# nixie2.net
KiCad netlist of a schematic drawn in EAGLE
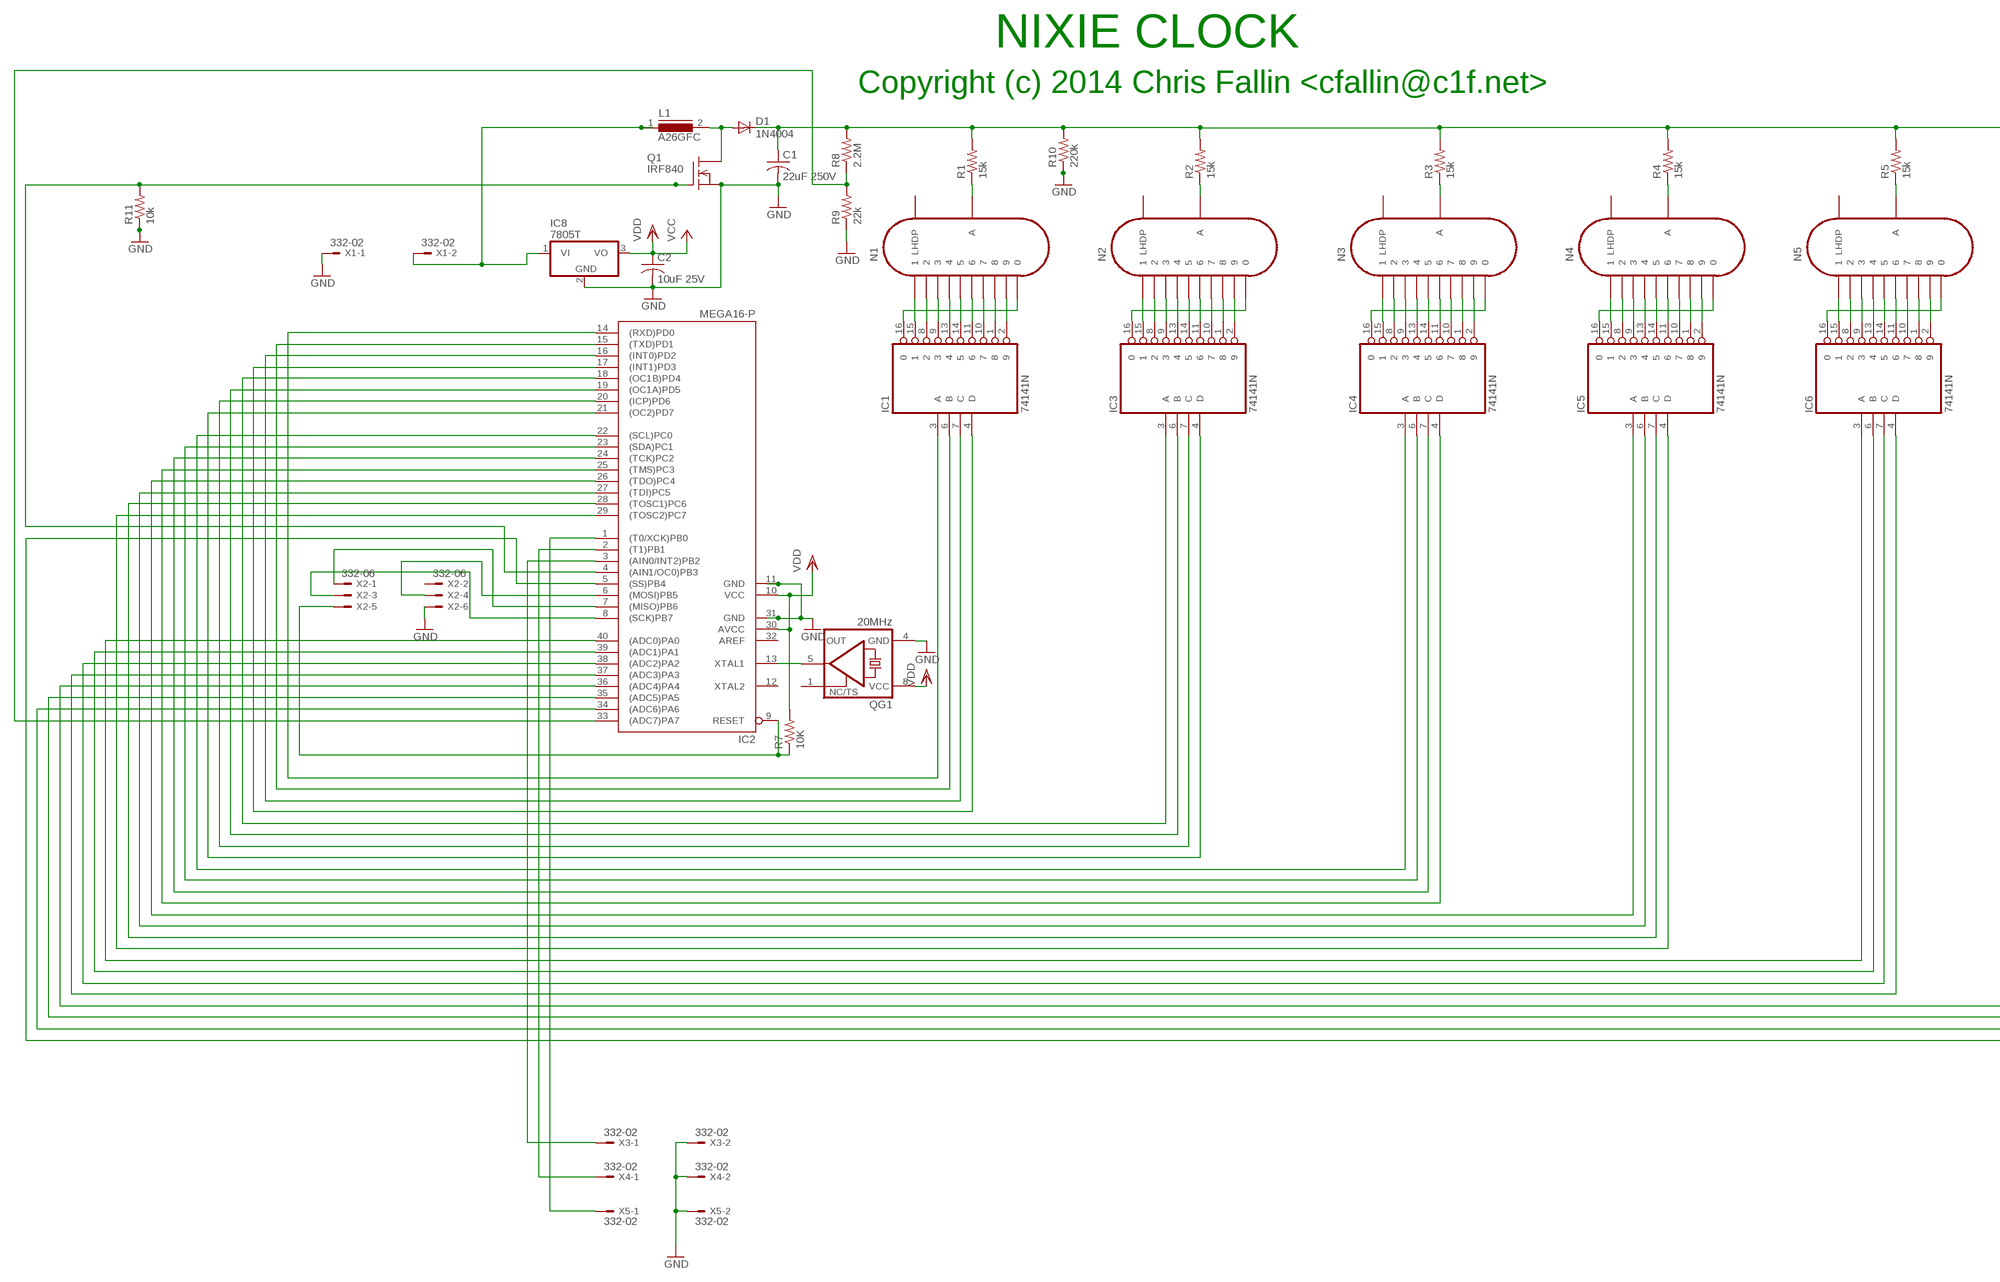
[diagram p0: schematic, sheet 1, part 1 of 2]
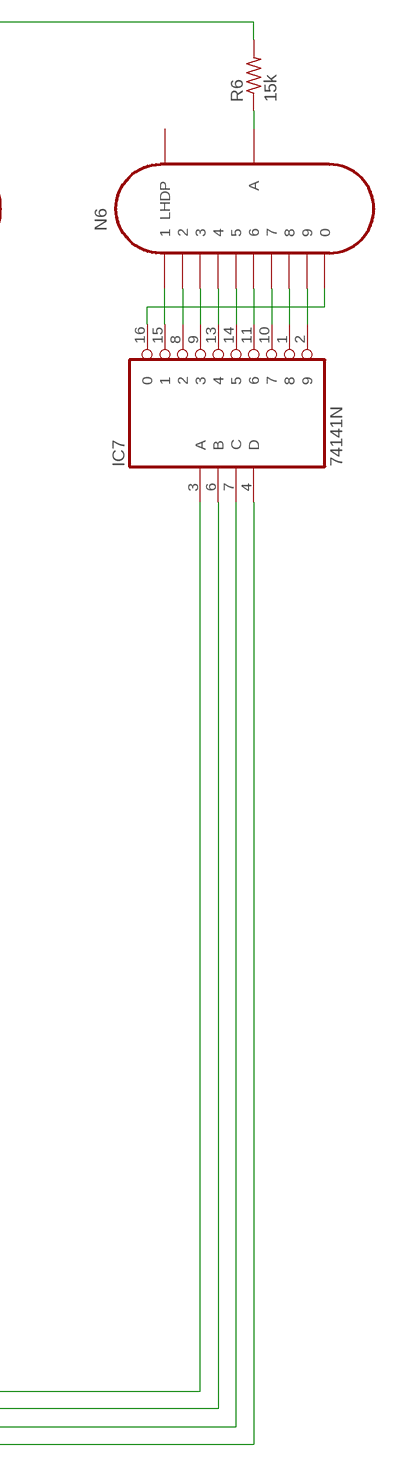
[diagram p1: schematic, sheet 1, part 2 of 2]

(export (version "E")
  (design (tool "Eeschema 10.0.6"))
  (components
    (comp (ref "C1")
      (value "22uF 250V")
      (footprint "eagle-import:C050-075X075")
      (libsource (lib "eagle-import") (part "C-US050-075X075"))
    )
    (comp (ref "C2")
      (value "10uF 25V")
      (footprint "eagle-import:C050-075X075")
      (libsource (lib "eagle-import") (part "C-US050-075X075"))
    )
    (comp (ref "D1")
      (value "1N4004")
      (footprint "eagle-import:DO41-10")
      (libsource (lib "eagle-import") (part "1N4004"))
    )
    (comp (ref "IC1")
      (value "74141N")
      (footprint "eagle-import:DIL16")
      (libsource (lib "eagle-import") (part "74141N"))
    )
    (comp (ref "IC2")
      (value "MEGA16-P")
      (footprint "eagle-import:DIL40")
      (fields (field (name "MPN") "ATMEGA16-16PU"))
      (libsource (lib "eagle-import") (part "MEGA16-P"))
    )
    (comp (ref "IC3")
      (value "74141N")
      (footprint "eagle-import:DIL16")
      (libsource (lib "eagle-import") (part "74141N"))
    )
    (comp (ref "IC4")
      (value "74141N")
      (footprint "eagle-import:DIL16")
      (libsource (lib "eagle-import") (part "74141N"))
    )
    (comp (ref "IC5")
      (value "74141N")
      (footprint "eagle-import:DIL16")
      (libsource (lib "eagle-import") (part "74141N"))
    )
    (comp (ref "IC6")
      (value "74141N")
      (footprint "eagle-import:DIL16")
      (libsource (lib "eagle-import") (part "74141N"))
    )
    (comp (ref "IC7")
      (value "74141N")
      (footprint "eagle-import:DIL16")
      (libsource (lib "eagle-import") (part "74141N"))
    )
    (comp (ref "IC8")
      (value "7805T")
      (footprint "eagle-import:TO220H")
      (libsource (lib "eagle-import") (part "78T05"))
    )
    (comp (ref "L1")
      (value "A26GFC")
      (footprint "eagle-import:A26GFC")
      (libsource (lib "eagle-import") (part "A26GFC"))
    )
    (comp (ref "N1")
      (value "IN-12B")
      (footprint "eagle-import:IN-12")
      (libsource (lib "eagle-import") (part "IN-12B"))
    )
    (comp (ref "N2")
      (value "IN-12B")
      (footprint "eagle-import:IN-12")
      (libsource (lib "eagle-import") (part "IN-12B"))
    )
    (comp (ref "N3")
      (value "IN-12B")
      (footprint "eagle-import:IN-12")
      (libsource (lib "eagle-import") (part "IN-12B"))
    )
    (comp (ref "N4")
      (value "IN-12B")
      (footprint "eagle-import:IN-12")
      (libsource (lib "eagle-import") (part "IN-12B"))
    )
    (comp (ref "N5")
      (value "IN-12B")
      (footprint "eagle-import:IN-12")
      (libsource (lib "eagle-import") (part "IN-12B"))
    )
    (comp (ref "N6")
      (value "IN-12B")
      (footprint "eagle-import:IN-12")
      (libsource (lib "eagle-import") (part "IN-12B"))
    )
    (comp (ref "Q1")
      (value "IRF840")
      (footprint "eagle-import:TO220")
      (libsource (lib "eagle-import") (part "IRF840"))
    )
    (comp (ref "QG1")
      (value "20MHz")
      (footprint "eagle-import:DIL08S")
      (libsource (lib "eagle-import") (part "XO-8"))
    )
    (comp (ref "R1")
      (value "15k")
      (footprint "eagle-import:0204V")
      (libsource (lib "eagle-import") (part "R-US_0204/2V"))
    )
    (comp (ref "R2")
      (value "15k")
      (footprint "eagle-import:0204V")
      (libsource (lib "eagle-import") (part "R-US_0204/2V"))
    )
    (comp (ref "R3")
      (value "15k")
      (footprint "eagle-import:0204V")
      (libsource (lib "eagle-import") (part "R-US_0204/2V"))
    )
    (comp (ref "R4")
      (value "15k")
      (footprint "eagle-import:0204V")
      (libsource (lib "eagle-import") (part "R-US_0204/2V"))
    )
    (comp (ref "R5")
      (value "15k")
      (footprint "eagle-import:0204V")
      (libsource (lib "eagle-import") (part "R-US_0204/2V"))
    )
    (comp (ref "R6")
      (value "15k")
      (footprint "eagle-import:0204V")
      (libsource (lib "eagle-import") (part "R-US_0204/2V"))
    )
    (comp (ref "R7")
      (value "10K")
      (footprint "eagle-import:0204V")
      (libsource (lib "eagle-import") (part "R-US_0204/2V"))
    )
    (comp (ref "R8")
      (value "2.2M")
      (footprint "eagle-import:0204V")
      (libsource (lib "eagle-import") (part "R-US_0204/2V"))
    )
    (comp (ref "R9")
      (value "22k")
      (footprint "eagle-import:0204V")
      (libsource (lib "eagle-import") (part "R-US_0204/2V"))
    )
    (comp (ref "R10")
      (value "220k")
      (footprint "eagle-import:0204V")
      (libsource (lib "eagle-import") (part "R-US_0204/2V"))
    )
    (comp (ref "R11")
      (value "10k")
      (footprint "eagle-import:0204V")
      (libsource (lib "eagle-import") (part "R-US_0204/2V"))
    )
    (comp (ref "X1")
      (value "332-02")
      (footprint "eagle-import:332-02")
      (libsource (lib "eagle-import") (part "332-02"))
    )
    (comp (ref "X2")
      (value "332-06")
      (footprint "eagle-import:332-06")
      (libsource (lib "eagle-import") (part "332-06"))
    )
    (comp (ref "X3")
      (value "332-02")
      (footprint "eagle-import:332-02")
      (libsource (lib "eagle-import") (part "332-02"))
    )
    (comp (ref "X4")
      (value "332-02")
      (footprint "eagle-import:332-02")
      (libsource (lib "eagle-import") (part "332-02"))
    )
    (comp (ref "X5")
      (value "332-02")
      (footprint "eagle-import:332-02")
      (libsource (lib "eagle-import") (part "332-02"))
    )
  )
  (nets
    (net (code "1") (name "GND") (class "Default")
      (node (ref "C1") (pin "2") (pinfunction "2_2") (pintype "passive"))
      (node (ref "C2") (pin "2") (pinfunction "2_2") (pintype "passive"))
      (node (ref "IC2") (pin "11") (pinfunction "GND_11") (pintype "power_in"))
      (node (ref "IC2") (pin "31") (pinfunction "GND_31") (pintype "power_in"))
      (node (ref "IC8") (pin "2") (pinfunction "GND_2") (pintype "passive"))
      (node (ref "Q1") (pin "3") (pinfunction "S_3") (pintype "passive"))
      (node (ref "QG1") (pin "4") (pinfunction "GND_4") (pintype "power_in"))
      (node (ref "R10") (pin "1") (pinfunction "1_1") (pintype "passive"))
      (node (ref "R11") (pin "1") (pinfunction "1_1") (pintype "passive"))
      (node (ref "R9") (pin "1") (pinfunction "1_1") (pintype "passive"))
      (node (ref "X1") (pin "1") (pinfunction "S_1") (pintype "passive"))
      (node (ref "X2") (pin "6") (pinfunction "S_6") (pintype "passive"))
      (node (ref "X3") (pin "2") (pinfunction "S_2") (pintype "passive"))
      (node (ref "X4") (pin "2") (pinfunction "S_2") (pintype "passive"))
      (node (ref "X5") (pin "2") (pinfunction "S_2") (pintype "passive"))
    )
    (net (code "2") (name "Net-(C1-Pad1)") (class "Default")
      (node (ref "C1") (pin "1") (pinfunction "1_1") (pintype "passive"))
      (node (ref "D1") (pin "C") (pinfunction "C_C") (pintype "passive"))
      (node (ref "R1") (pin "2") (pinfunction "2_2") (pintype "passive"))
      (node (ref "R10") (pin "2") (pinfunction "2_2") (pintype "passive"))
      (node (ref "R2") (pin "2") (pinfunction "2_2") (pintype "passive"))
      (node (ref "R3") (pin "2") (pinfunction "2_2") (pintype "passive"))
      (node (ref "R4") (pin "2") (pinfunction "2_2") (pintype "passive"))
      (node (ref "R5") (pin "2") (pinfunction "2_2") (pintype "passive"))
      (node (ref "R6") (pin "2") (pinfunction "2_2") (pintype "passive"))
      (node (ref "R8") (pin "2") (pinfunction "2_2") (pintype "passive"))
    )
    (net (code "3") (name "Net-(IC1A-0)") (class "Default")
      (node (ref "IC1") (pin "16") (pinfunction "0_16") (pintype "open_collector"))
      (node (ref "N1") (pin "0") (pinfunction "0_0") (pintype "bidirectional"))
    )
    (net (code "4") (name "Net-(IC1A-1)") (class "Default")
      (node (ref "IC1") (pin "15") (pinfunction "1_15") (pintype "open_collector"))
      (node (ref "N1") (pin "1") (pinfunction "1_1") (pintype "bidirectional"))
    )
    (net (code "5") (name "Net-(IC1A-2)") (class "Default")
      (node (ref "IC1") (pin "8") (pinfunction "2_8") (pintype "open_collector"))
      (node (ref "N1") (pin "2") (pinfunction "2_2") (pintype "bidirectional"))
    )
    (net (code "6") (name "Net-(IC1A-3)") (class "Default")
      (node (ref "IC1") (pin "9") (pinfunction "3_9") (pintype "open_collector"))
      (node (ref "N1") (pin "3") (pinfunction "3_3") (pintype "bidirectional"))
    )
    (net (code "7") (name "Net-(IC1A-4)") (class "Default")
      (node (ref "IC1") (pin "13") (pinfunction "4_13") (pintype "open_collector"))
      (node (ref "N1") (pin "4") (pinfunction "4_4") (pintype "bidirectional"))
    )
    (net (code "8") (name "Net-(IC1A-5)") (class "Default")
      (node (ref "IC1") (pin "14") (pinfunction "5_14") (pintype "open_collector"))
      (node (ref "N1") (pin "5") (pinfunction "5_5") (pintype "bidirectional"))
    )
    (net (code "9") (name "Net-(IC1A-6)") (class "Default")
      (node (ref "IC1") (pin "11") (pinfunction "6_11") (pintype "open_collector"))
      (node (ref "N1") (pin "6") (pinfunction "6_6") (pintype "bidirectional"))
    )
    (net (code "10") (name "Net-(IC1A-7)") (class "Default")
      (node (ref "IC1") (pin "10") (pinfunction "7_10") (pintype "open_collector"))
      (node (ref "N1") (pin "7") (pinfunction "7_7") (pintype "bidirectional"))
    )
    (net (code "11") (name "Net-(IC1A-8)") (class "Default")
      (node (ref "IC1") (pin "1") (pinfunction "8_1") (pintype "open_collector"))
      (node (ref "N1") (pin "8") (pinfunction "8_8") (pintype "bidirectional"))
    )
    (net (code "12") (name "Net-(IC1A-9)") (class "Default")
      (node (ref "IC1") (pin "2") (pinfunction "9_2") (pintype "open_collector"))
      (node (ref "N1") (pin "9") (pinfunction "9_9") (pintype "bidirectional"))
    )
    (net (code "13") (name "Net-(IC1A-A)") (class "Default")
      (node (ref "IC1") (pin "3") (pinfunction "A_3") (pintype "input"))
      (node (ref "IC2") (pin "14") (pinfunction "(RXD)PD0_14") (pintype "bidirectional"))
    )
    (net (code "14") (name "Net-(IC1A-B)") (class "Default")
      (node (ref "IC1") (pin "6") (pinfunction "B_6") (pintype "input"))
      (node (ref "IC2") (pin "15") (pinfunction "(TXD)PD1_15") (pintype "bidirectional"))
    )
    (net (code "15") (name "Net-(IC1A-C)") (class "Default")
      (node (ref "IC1") (pin "7") (pinfunction "C_7") (pintype "input"))
      (node (ref "IC2") (pin "16") (pinfunction "(INT0)PD2_16") (pintype "bidirectional"))
    )
    (net (code "16") (name "Net-(IC1A-D)") (class "Default")
      (node (ref "IC1") (pin "4") (pinfunction "D_4") (pintype "input"))
      (node (ref "IC2") (pin "17") (pinfunction "(INT1)PD3_17") (pintype "bidirectional"))
    )
    (net (code "17") (name "Net-(IC2-(ADC0)PA0)") (class "Default")
      (node (ref "IC2") (pin "40") (pinfunction "(ADC0)PA0_40") (pintype "bidirectional"))
      (node (ref "IC6") (pin "3") (pinfunction "A_3") (pintype "input"))
    )
    (net (code "18") (name "Net-(IC2-(ADC1)PA1)") (class "Default")
      (node (ref "IC2") (pin "39") (pinfunction "(ADC1)PA1_39") (pintype "bidirectional"))
      (node (ref "IC6") (pin "6") (pinfunction "B_6") (pintype "input"))
    )
    (net (code "19") (name "Net-(IC2-(ADC2)PA2)") (class "Default")
      (node (ref "IC2") (pin "38") (pinfunction "(ADC2)PA2_38") (pintype "bidirectional"))
      (node (ref "IC6") (pin "7") (pinfunction "C_7") (pintype "input"))
    )
    (net (code "20") (name "Net-(IC2-(ADC3)PA3)") (class "Default")
      (node (ref "IC2") (pin "37") (pinfunction "(ADC3)PA3_37") (pintype "bidirectional"))
      (node (ref "IC6") (pin "4") (pinfunction "D_4") (pintype "input"))
    )
    (net (code "21") (name "Net-(IC2-(ADC4)PA4)") (class "Default")
      (node (ref "IC2") (pin "36") (pinfunction "(ADC4)PA4_36") (pintype "bidirectional"))
      (node (ref "IC7") (pin "3") (pinfunction "A_3") (pintype "input"))
    )
    (net (code "22") (name "Net-(IC2-(ADC5)PA5)") (class "Default")
      (node (ref "IC2") (pin "35") (pinfunction "(ADC5)PA5_35") (pintype "bidirectional"))
      (node (ref "IC7") (pin "6") (pinfunction "B_6") (pintype "input"))
    )
    (net (code "23") (name "Net-(IC2-(ADC6)PA6)") (class "Default")
      (node (ref "IC2") (pin "34") (pinfunction "(ADC6)PA6_34") (pintype "bidirectional"))
      (node (ref "IC7") (pin "7") (pinfunction "C_7") (pintype "input"))
    )
    (net (code "24") (name "Net-(IC2-(ADC7)PA7)") (class "Default")
      (node (ref "IC2") (pin "33") (pinfunction "(ADC7)PA7_33") (pintype "bidirectional"))
      (node (ref "R8") (pin "1") (pinfunction "1_1") (pintype "passive"))
      (node (ref "R9") (pin "2") (pinfunction "2_2") (pintype "passive"))
    )
    (net (code "25") (name "Net-(IC2-(AIN0{slash}INT2)PB2)") (class "Default")
      (node (ref "IC2") (pin "3") (pinfunction "(AIN0/INT2)PB2_3") (pintype "bidirectional"))
      (node (ref "X3") (pin "1") (pinfunction "S_1") (pintype "passive"))
    )
    (net (code "26") (name "Net-(IC2-(AIN1{slash}OC0)PB3)") (class "Default")
      (node (ref "IC2") (pin "4") (pinfunction "(AIN1/OC0)PB3_4") (pintype "bidirectional"))
      (node (ref "Q1") (pin "1") (pinfunction "G_1") (pintype "passive"))
      (node (ref "R11") (pin "2") (pinfunction "2_2") (pintype "passive"))
    )
    (net (code "27") (name "Net-(IC2-(ICP)PD6)") (class "Default")
      (node (ref "IC2") (pin "20") (pinfunction "(ICP)PD6_20") (pintype "bidirectional"))
      (node (ref "IC3") (pin "7") (pinfunction "C_7") (pintype "input"))
    )
    (net (code "28") (name "Net-(IC2-(MISO)PB6)") (class "Default")
      (node (ref "IC2") (pin "7") (pinfunction "(MISO)PB6_7") (pintype "bidirectional"))
      (node (ref "X2") (pin "1") (pinfunction "S_1") (pintype "passive"))
    )
    (net (code "29") (name "Net-(IC2-(MOSI)PB5)") (class "Default")
      (node (ref "IC2") (pin "6") (pinfunction "(MOSI)PB5_6") (pintype "bidirectional"))
      (node (ref "X2") (pin "4") (pinfunction "S_4") (pintype "passive"))
    )
    (net (code "30") (name "Net-(IC2-(OC1A)PD5)") (class "Default")
      (node (ref "IC2") (pin "19") (pinfunction "(OC1A)PD5_19") (pintype "bidirectional"))
      (node (ref "IC3") (pin "6") (pinfunction "B_6") (pintype "input"))
    )
    (net (code "31") (name "Net-(IC2-(OC1B)PD4)") (class "Default")
      (node (ref "IC2") (pin "18") (pinfunction "(OC1B)PD4_18") (pintype "bidirectional"))
      (node (ref "IC3") (pin "3") (pinfunction "A_3") (pintype "input"))
    )
    (net (code "32") (name "Net-(IC2-(OC2)PD7)") (class "Default")
      (node (ref "IC2") (pin "21") (pinfunction "(OC2)PD7_21") (pintype "bidirectional"))
      (node (ref "IC3") (pin "4") (pinfunction "D_4") (pintype "input"))
    )
    (net (code "33") (name "Net-(IC2-(SCK)PB7)") (class "Default")
      (node (ref "IC2") (pin "8") (pinfunction "(SCK)PB7_8") (pintype "bidirectional"))
      (node (ref "X2") (pin "3") (pinfunction "S_3") (pintype "passive"))
    )
    (net (code "34") (name "Net-(IC2-(SCL)PC0)") (class "Default")
      (node (ref "IC2") (pin "22") (pinfunction "(SCL)PC0_22") (pintype "bidirectional"))
      (node (ref "IC4") (pin "3") (pinfunction "A_3") (pintype "input"))
    )
    (net (code "35") (name "Net-(IC2-(SDA)PC1)") (class "Default")
      (node (ref "IC2") (pin "23") (pinfunction "(SDA)PC1_23") (pintype "bidirectional"))
      (node (ref "IC4") (pin "6") (pinfunction "B_6") (pintype "input"))
    )
    (net (code "36") (name "Net-(IC2-(SS)PB4)") (class "Default")
      (node (ref "IC2") (pin "5") (pinfunction "(SS)PB4_5") (pintype "bidirectional"))
      (node (ref "IC7") (pin "4") (pinfunction "D_4") (pintype "input"))
    )
    (net (code "37") (name "Net-(IC2-(T0{slash}XCK)PB0)") (class "Default")
      (node (ref "IC2") (pin "1") (pinfunction "(T0/XCK)PB0_1") (pintype "bidirectional"))
      (node (ref "X5") (pin "1") (pinfunction "S_1") (pintype "passive"))
    )
    (net (code "38") (name "Net-(IC2-(T1)PB1)") (class "Default")
      (node (ref "IC2") (pin "2") (pinfunction "(T1)PB1_2") (pintype "bidirectional"))
      (node (ref "X4") (pin "1") (pinfunction "S_1") (pintype "passive"))
    )
    (net (code "39") (name "Net-(IC2-(TCK)PC2)") (class "Default")
      (node (ref "IC2") (pin "24") (pinfunction "(TCK)PC2_24") (pintype "bidirectional"))
      (node (ref "IC4") (pin "7") (pinfunction "C_7") (pintype "input"))
    )
    (net (code "40") (name "Net-(IC2-(TDI)PC5)") (class "Default")
      (node (ref "IC2") (pin "27") (pinfunction "(TDI)PC5_27") (pintype "bidirectional"))
      (node (ref "IC5") (pin "6") (pinfunction "B_6") (pintype "input"))
    )
    (net (code "41") (name "Net-(IC2-(TDO)PC4)") (class "Default")
      (node (ref "IC2") (pin "26") (pinfunction "(TDO)PC4_26") (pintype "bidirectional"))
      (node (ref "IC5") (pin "3") (pinfunction "A_3") (pintype "input"))
    )
    (net (code "42") (name "Net-(IC2-(TMS)PC3)") (class "Default")
      (node (ref "IC2") (pin "25") (pinfunction "(TMS)PC3_25") (pintype "bidirectional"))
      (node (ref "IC4") (pin "4") (pinfunction "D_4") (pintype "input"))
    )
    (net (code "43") (name "Net-(IC2-(TOSC1)PC6)") (class "Default")
      (node (ref "IC2") (pin "28") (pinfunction "(TOSC1)PC6_28") (pintype "bidirectional"))
      (node (ref "IC5") (pin "7") (pinfunction "C_7") (pintype "input"))
    )
    (net (code "44") (name "Net-(IC2-(TOSC2)PC7)") (class "Default")
      (node (ref "IC2") (pin "29") (pinfunction "(TOSC2)PC7_29") (pintype "bidirectional"))
      (node (ref "IC5") (pin "4") (pinfunction "D_4") (pintype "input"))
    )
    (net (code "45") (name "Net-(IC2-RESET)") (class "Default")
      (node (ref "IC2") (pin "9") (pinfunction "RESET_9") (pintype "input"))
      (node (ref "R7") (pin "1") (pinfunction "1_1") (pintype "passive"))
      (node (ref "X2") (pin "5") (pinfunction "S_5") (pintype "passive"))
    )
    (net (code "46") (name "Net-(IC2-XTAL1)") (class "Default")
      (node (ref "IC2") (pin "13") (pinfunction "XTAL1_13") (pintype "bidirectional"))
      (node (ref "QG1") (pin "5") (pinfunction "OUT_5") (pintype "output"))
    )
    (net (code "47") (name "Net-(IC3A-0)") (class "Default")
      (node (ref "IC3") (pin "16") (pinfunction "0_16") (pintype "open_collector"))
      (node (ref "N2") (pin "0") (pinfunction "0_0") (pintype "bidirectional"))
    )
    (net (code "48") (name "Net-(IC3A-1)") (class "Default")
      (node (ref "IC3") (pin "15") (pinfunction "1_15") (pintype "open_collector"))
      (node (ref "N2") (pin "1") (pinfunction "1_1") (pintype "bidirectional"))
    )
    (net (code "49") (name "Net-(IC3A-2)") (class "Default")
      (node (ref "IC3") (pin "8") (pinfunction "2_8") (pintype "open_collector"))
      (node (ref "N2") (pin "2") (pinfunction "2_2") (pintype "bidirectional"))
    )
    (net (code "50") (name "Net-(IC3A-3)") (class "Default")
      (node (ref "IC3") (pin "9") (pinfunction "3_9") (pintype "open_collector"))
      (node (ref "N2") (pin "3") (pinfunction "3_3") (pintype "bidirectional"))
    )
    (net (code "51") (name "Net-(IC3A-4)") (class "Default")
      (node (ref "IC3") (pin "13") (pinfunction "4_13") (pintype "open_collector"))
      (node (ref "N2") (pin "4") (pinfunction "4_4") (pintype "bidirectional"))
    )
    (net (code "52") (name "Net-(IC3A-5)") (class "Default")
      (node (ref "IC3") (pin "14") (pinfunction "5_14") (pintype "open_collector"))
      (node (ref "N2") (pin "5") (pinfunction "5_5") (pintype "bidirectional"))
    )
    (net (code "53") (name "Net-(IC3A-6)") (class "Default")
      (node (ref "IC3") (pin "11") (pinfunction "6_11") (pintype "open_collector"))
      (node (ref "N2") (pin "6") (pinfunction "6_6") (pintype "bidirectional"))
    )
    (net (code "54") (name "Net-(IC3A-7)") (class "Default")
      (node (ref "IC3") (pin "10") (pinfunction "7_10") (pintype "open_collector"))
      (node (ref "N2") (pin "7") (pinfunction "7_7") (pintype "bidirectional"))
    )
    (net (code "55") (name "Net-(IC3A-8)") (class "Default")
      (node (ref "IC3") (pin "1") (pinfunction "8_1") (pintype "open_collector"))
      (node (ref "N2") (pin "8") (pinfunction "8_8") (pintype "bidirectional"))
    )
    (net (code "56") (name "Net-(IC3A-9)") (class "Default")
      (node (ref "IC3") (pin "2") (pinfunction "9_2") (pintype "open_collector"))
      (node (ref "N2") (pin "9") (pinfunction "9_9") (pintype "bidirectional"))
    )
    (net (code "57") (name "Net-(IC4A-0)") (class "Default")
      (node (ref "IC4") (pin "16") (pinfunction "0_16") (pintype "open_collector"))
      (node (ref "N3") (pin "0") (pinfunction "0_0") (pintype "bidirectional"))
    )
    (net (code "58") (name "Net-(IC4A-1)") (class "Default")
      (node (ref "IC4") (pin "15") (pinfunction "1_15") (pintype "open_collector"))
      (node (ref "N3") (pin "1") (pinfunction "1_1") (pintype "bidirectional"))
    )
    (net (code "59") (name "Net-(IC4A-2)") (class "Default")
      (node (ref "IC4") (pin "8") (pinfunction "2_8") (pintype "open_collector"))
      (node (ref "N3") (pin "2") (pinfunction "2_2") (pintype "bidirectional"))
    )
    (net (code "60") (name "Net-(IC4A-3)") (class "Default")
      (node (ref "IC4") (pin "9") (pinfunction "3_9") (pintype "open_collector"))
      (node (ref "N3") (pin "3") (pinfunction "3_3") (pintype "bidirectional"))
    )
    (net (code "61") (name "Net-(IC4A-4)") (class "Default")
      (node (ref "IC4") (pin "13") (pinfunction "4_13") (pintype "open_collector"))
      (node (ref "N3") (pin "4") (pinfunction "4_4") (pintype "bidirectional"))
    )
    (net (code "62") (name "Net-(IC4A-5)") (class "Default")
      (node (ref "IC4") (pin "14") (pinfunction "5_14") (pintype "open_collector"))
      (node (ref "N3") (pin "5") (pinfunction "5_5") (pintype "bidirectional"))
    )
    (net (code "63") (name "Net-(IC4A-6)") (class "Default")
      (node (ref "IC4") (pin "11") (pinfunction "6_11") (pintype "open_collector"))
      (node (ref "N3") (pin "6") (pinfunction "6_6") (pintype "bidirectional"))
    )
    (net (code "64") (name "Net-(IC4A-7)") (class "Default")
      (node (ref "IC4") (pin "10") (pinfunction "7_10") (pintype "open_collector"))
      (node (ref "N3") (pin "7") (pinfunction "7_7") (pintype "bidirectional"))
    )
    (net (code "65") (name "Net-(IC4A-8)") (class "Default")
      (node (ref "IC4") (pin "1") (pinfunction "8_1") (pintype "open_collector"))
      (node (ref "N3") (pin "8") (pinfunction "8_8") (pintype "bidirectional"))
    )
    (net (code "66") (name "Net-(IC4A-9)") (class "Default")
      (node (ref "IC4") (pin "2") (pinfunction "9_2") (pintype "open_collector"))
      (node (ref "N3") (pin "9") (pinfunction "9_9") (pintype "bidirectional"))
    )
    (net (code "67") (name "Net-(IC5A-0)") (class "Default")
      (node (ref "IC5") (pin "16") (pinfunction "0_16") (pintype "open_collector"))
      (node (ref "N4") (pin "0") (pinfunction "0_0") (pintype "bidirectional"))
    )
    (net (code "68") (name "Net-(IC5A-1)") (class "Default")
      (node (ref "IC5") (pin "15") (pinfunction "1_15") (pintype "open_collector"))
      (node (ref "N4") (pin "1") (pinfunction "1_1") (pintype "bidirectional"))
    )
    (net (code "69") (name "Net-(IC5A-2)") (class "Default")
      (node (ref "IC5") (pin "8") (pinfunction "2_8") (pintype "open_collector"))
      (node (ref "N4") (pin "2") (pinfunction "2_2") (pintype "bidirectional"))
    )
    (net (code "70") (name "Net-(IC5A-3)") (class "Default")
      (node (ref "IC5") (pin "9") (pinfunction "3_9") (pintype "open_collector"))
      (node (ref "N4") (pin "3") (pinfunction "3_3") (pintype "bidirectional"))
    )
    (net (code "71") (name "Net-(IC5A-4)") (class "Default")
      (node (ref "IC5") (pin "13") (pinfunction "4_13") (pintype "open_collector"))
      (node (ref "N4") (pin "4") (pinfunction "4_4") (pintype "bidirectional"))
    )
    (net (code "72") (name "Net-(IC5A-5)") (class "Default")
      (node (ref "IC5") (pin "14") (pinfunction "5_14") (pintype "open_collector"))
      (node (ref "N4") (pin "5") (pinfunction "5_5") (pintype "bidirectional"))
    )
    (net (code "73") (name "Net-(IC5A-6)") (class "Default")
      (node (ref "IC5") (pin "11") (pinfunction "6_11") (pintype "open_collector"))
      (node (ref "N4") (pin "6") (pinfunction "6_6") (pintype "bidirectional"))
    )
    (net (code "74") (name "Net-(IC5A-7)") (class "Default")
      (node (ref "IC5") (pin "10") (pinfunction "7_10") (pintype "open_collector"))
      (node (ref "N4") (pin "7") (pinfunction "7_7") (pintype "bidirectional"))
    )
    (net (code "75") (name "Net-(IC5A-8)") (class "Default")
      (node (ref "IC5") (pin "1") (pinfunction "8_1") (pintype "open_collector"))
      (node (ref "N4") (pin "8") (pinfunction "8_8") (pintype "bidirectional"))
    )
    (net (code "76") (name "Net-(IC5A-9)") (class "Default")
      (node (ref "IC5") (pin "2") (pinfunction "9_2") (pintype "open_collector"))
      (node (ref "N4") (pin "9") (pinfunction "9_9") (pintype "bidirectional"))
    )
    (net (code "77") (name "Net-(IC6A-0)") (class "Default")
      (node (ref "IC6") (pin "16") (pinfunction "0_16") (pintype "open_collector"))
      (node (ref "N5") (pin "0") (pinfunction "0_0") (pintype "bidirectional"))
    )
    (net (code "78") (name "Net-(IC6A-1)") (class "Default")
      (node (ref "IC6") (pin "15") (pinfunction "1_15") (pintype "open_collector"))
      (node (ref "N5") (pin "1") (pinfunction "1_1") (pintype "bidirectional"))
    )
    (net (code "79") (name "Net-(IC6A-2)") (class "Default")
      (node (ref "IC6") (pin "8") (pinfunction "2_8") (pintype "open_collector"))
      (node (ref "N5") (pin "2") (pinfunction "2_2") (pintype "bidirectional"))
    )
    (net (code "80") (name "Net-(IC6A-3)") (class "Default")
      (node (ref "IC6") (pin "9") (pinfunction "3_9") (pintype "open_collector"))
      (node (ref "N5") (pin "3") (pinfunction "3_3") (pintype "bidirectional"))
    )
    (net (code "81") (name "Net-(IC6A-4)") (class "Default")
      (node (ref "IC6") (pin "13") (pinfunction "4_13") (pintype "open_collector"))
      (node (ref "N5") (pin "4") (pinfunction "4_4") (pintype "bidirectional"))
    )
    (net (code "82") (name "Net-(IC6A-5)") (class "Default")
      (node (ref "IC6") (pin "14") (pinfunction "5_14") (pintype "open_collector"))
      (node (ref "N5") (pin "5") (pinfunction "5_5") (pintype "bidirectional"))
    )
    (net (code "83") (name "Net-(IC6A-6)") (class "Default")
      (node (ref "IC6") (pin "11") (pinfunction "6_11") (pintype "open_collector"))
      (node (ref "N5") (pin "6") (pinfunction "6_6") (pintype "bidirectional"))
    )
    (net (code "84") (name "Net-(IC6A-7)") (class "Default")
      (node (ref "IC6") (pin "10") (pinfunction "7_10") (pintype "open_collector"))
      (node (ref "N5") (pin "7") (pinfunction "7_7") (pintype "bidirectional"))
    )
    (net (code "85") (name "Net-(IC6A-8)") (class "Default")
      (node (ref "IC6") (pin "1") (pinfunction "8_1") (pintype "open_collector"))
      (node (ref "N5") (pin "8") (pinfunction "8_8") (pintype "bidirectional"))
    )
    (net (code "86") (name "Net-(IC6A-9)") (class "Default")
      (node (ref "IC6") (pin "2") (pinfunction "9_2") (pintype "open_collector"))
      (node (ref "N5") (pin "9") (pinfunction "9_9") (pintype "bidirectional"))
    )
    (net (code "87") (name "Net-(IC7A-0)") (class "Default")
      (node (ref "IC7") (pin "16") (pinfunction "0_16") (pintype "open_collector"))
      (node (ref "N6") (pin "0") (pinfunction "0_0") (pintype "bidirectional"))
    )
    (net (code "88") (name "Net-(IC7A-1)") (class "Default")
      (node (ref "IC7") (pin "15") (pinfunction "1_15") (pintype "open_collector"))
      (node (ref "N6") (pin "1") (pinfunction "1_1") (pintype "bidirectional"))
    )
    (net (code "89") (name "Net-(IC7A-2)") (class "Default")
      (node (ref "IC7") (pin "8") (pinfunction "2_8") (pintype "open_collector"))
      (node (ref "N6") (pin "2") (pinfunction "2_2") (pintype "bidirectional"))
    )
    (net (code "90") (name "Net-(IC7A-3)") (class "Default")
      (node (ref "IC7") (pin "9") (pinfunction "3_9") (pintype "open_collector"))
      (node (ref "N6") (pin "3") (pinfunction "3_3") (pintype "bidirectional"))
    )
    (net (code "91") (name "Net-(IC7A-4)") (class "Default")
      (node (ref "IC7") (pin "13") (pinfunction "4_13") (pintype "open_collector"))
      (node (ref "N6") (pin "4") (pinfunction "4_4") (pintype "bidirectional"))
    )
    (net (code "92") (name "Net-(IC7A-5)") (class "Default")
      (node (ref "IC7") (pin "14") (pinfunction "5_14") (pintype "open_collector"))
      (node (ref "N6") (pin "5") (pinfunction "5_5") (pintype "bidirectional"))
    )
    (net (code "93") (name "Net-(IC7A-6)") (class "Default")
      (node (ref "IC7") (pin "11") (pinfunction "6_11") (pintype "open_collector"))
      (node (ref "N6") (pin "6") (pinfunction "6_6") (pintype "bidirectional"))
    )
    (net (code "94") (name "Net-(IC7A-7)") (class "Default")
      (node (ref "IC7") (pin "10") (pinfunction "7_10") (pintype "open_collector"))
      (node (ref "N6") (pin "7") (pinfunction "7_7") (pintype "bidirectional"))
    )
    (net (code "95") (name "Net-(IC7A-8)") (class "Default")
      (node (ref "IC7") (pin "1") (pinfunction "8_1") (pintype "open_collector"))
      (node (ref "N6") (pin "8") (pinfunction "8_8") (pintype "bidirectional"))
    )
    (net (code "96") (name "Net-(IC7A-9)") (class "Default")
      (node (ref "IC7") (pin "2") (pinfunction "9_2") (pintype "open_collector"))
      (node (ref "N6") (pin "9") (pinfunction "9_9") (pintype "bidirectional"))
    )
    (net (code "97") (name "Net-(IC8-VI)") (class "Default")
      (node (ref "IC8") (pin "1") (pinfunction "VI_1") (pintype "input"))
      (node (ref "L1") (pin "1") (pinfunction "1_1") (pintype "passive"))
      (node (ref "X1") (pin "2") (pinfunction "S_2") (pintype "passive"))
    )
    (net (code "98") (name "Net-(N1-PadA)") (class "Default")
      (node (ref "N1") (pin "A") (pinfunction "A_A") (pintype "bidirectional"))
      (node (ref "R1") (pin "1") (pinfunction "1_1") (pintype "passive"))
    )
    (net (code "99") (name "Net-(N2-PadA)") (class "Default")
      (node (ref "N2") (pin "A") (pinfunction "A_A") (pintype "bidirectional"))
      (node (ref "R2") (pin "1") (pinfunction "1_1") (pintype "passive"))
    )
    (net (code "100") (name "Net-(N3-PadA)") (class "Default")
      (node (ref "N3") (pin "A") (pinfunction "A_A") (pintype "bidirectional"))
      (node (ref "R3") (pin "1") (pinfunction "1_1") (pintype "passive"))
    )
    (net (code "101") (name "Net-(N4-PadA)") (class "Default")
      (node (ref "N4") (pin "A") (pinfunction "A_A") (pintype "bidirectional"))
      (node (ref "R4") (pin "1") (pinfunction "1_1") (pintype "passive"))
    )
    (net (code "102") (name "Net-(N5-PadA)") (class "Default")
      (node (ref "N5") (pin "A") (pinfunction "A_A") (pintype "bidirectional"))
      (node (ref "R5") (pin "1") (pinfunction "1_1") (pintype "passive"))
    )
    (net (code "103") (name "Net-(N6-PadA)") (class "Default")
      (node (ref "N6") (pin "A") (pinfunction "A_A") (pintype "bidirectional"))
      (node (ref "R6") (pin "1") (pinfunction "1_1") (pintype "passive"))
    )
    (net (code "104") (name "Net-(Q1-D)") (class "Default")
      (node (ref "D1") (pin "A") (pinfunction "A_A") (pintype "passive"))
      (node (ref "L1") (pin "2") (pinfunction "2_2") (pintype "passive"))
      (node (ref "Q1") (pin "2") (pinfunction "D_2") (pintype "passive"))
    )
    (net (code "105") (name "VCC") (class "Default")
      (node (ref "C2") (pin "1") (pinfunction "1_1") (pintype "passive"))
      (node (ref "IC2") (pin "10") (pinfunction "VCC_10") (pintype "power_in"))
      (node (ref "IC2") (pin "30") (pinfunction "AVCC_30") (pintype "power_in"))
      (node (ref "IC8") (pin "3") (pinfunction "VO_3") (pintype "passive"))
      (node (ref "QG1") (pin "8") (pinfunction "VCC_8") (pintype "power_in"))
      (node (ref "R7") (pin "2") (pinfunction "2_2") (pintype "passive"))
    )
    (net (code "106") (name "unconnected-(IC2-AREF-Pad32)") (class "Default")
      (node (ref "IC2") (pin "32") (pinfunction "AREF_32") (pintype "passive"))
    )
    (net (code "107") (name "unconnected-(IC2-XTAL2-Pad12)") (class "Default")
      (node (ref "IC2") (pin "12") (pinfunction "XTAL2_12") (pintype "bidirectional"))
    )
    (net (code "108") (name "unconnected-(N1-PadLHDP)") (class "Default")
      (node (ref "N1") (pin "LHDP") (pinfunction "LHDP_LHDP") (pintype "bidirectional"))
    )
    (net (code "109") (name "unconnected-(N2-PadLHDP)") (class "Default")
      (node (ref "N2") (pin "LHDP") (pinfunction "LHDP_LHDP") (pintype "bidirectional"))
    )
    (net (code "110") (name "unconnected-(N3-PadLHDP)") (class "Default")
      (node (ref "N3") (pin "LHDP") (pinfunction "LHDP_LHDP") (pintype "bidirectional"))
    )
    (net (code "111") (name "unconnected-(N4-PadLHDP)") (class "Default")
      (node (ref "N4") (pin "LHDP") (pinfunction "LHDP_LHDP") (pintype "bidirectional"))
    )
    (net (code "112") (name "unconnected-(N5-PadLHDP)") (class "Default")
      (node (ref "N5") (pin "LHDP") (pinfunction "LHDP_LHDP") (pintype "bidirectional"))
    )
    (net (code "113") (name "unconnected-(N6-PadLHDP)") (class "Default")
      (node (ref "N6") (pin "LHDP") (pinfunction "LHDP_LHDP") (pintype "bidirectional"))
    )
    (net (code "114") (name "unconnected-(QG1-TS-Pad1)") (class "Default")
      (node (ref "QG1") (pin "1") (pinfunction "TS_1") (pintype "passive"))
    )
    (net (code "115") (name "unconnected-(X2B-S-Pad2)") (class "Default")
      (node (ref "X2") (pin "2") (pinfunction "S_2") (pintype "passive"))
    )
  )
)
